# P10_ESP32_1.net
KiCad netlist of a schematic drawn in Altium Designer
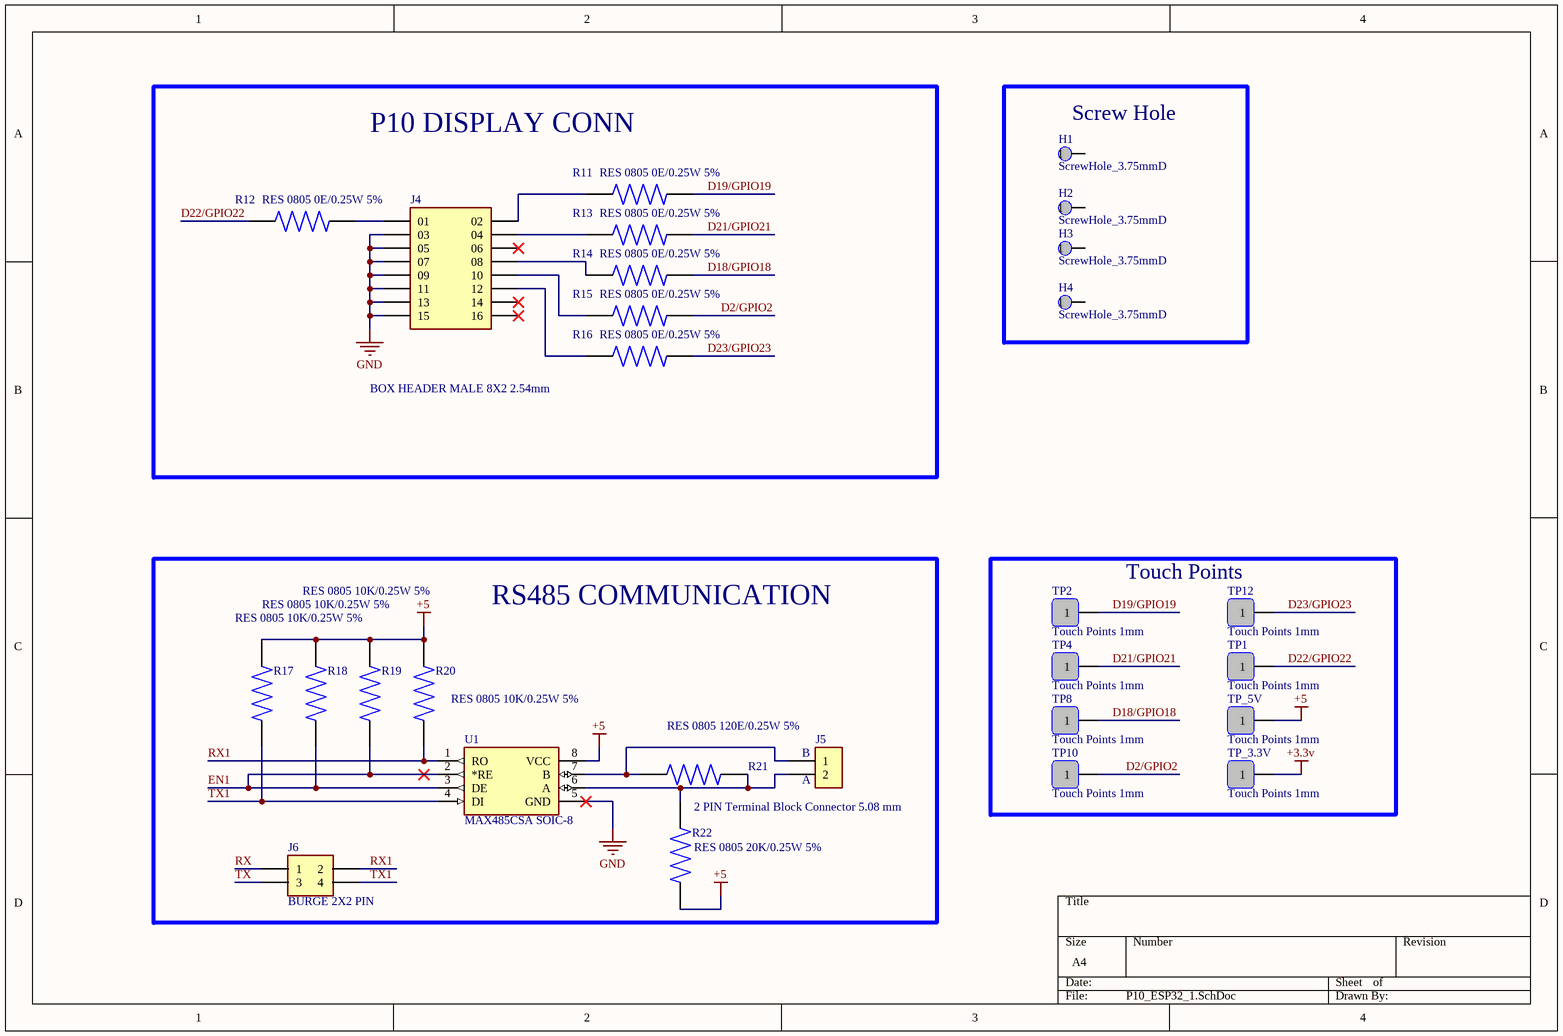
[diagram p0: P10_ESP32_1.SchDoc]

(export (version "E")
  (design (tool "Eeschema 10.0.6"))
  (components
    (comp (ref "H1")
      (value "ScrewHole_3.75mmD")
      (footprint "ScrewHole_3.75mmD")
      (description "SCREW HEAD DIA 4.5MM, SREW LEG DIA 3 MM")
      (libsource (lib "P10_ESP32") (part "ScrewHole_3.75mmD"))
    )
    (comp (ref "H2")
      (value "ScrewHole_3.75mmD")
      (footprint "ScrewHole_3.75mmD")
      (description "SCREW HEAD DIA 4.5MM, SREW LEG DIA 3 MM")
      (libsource (lib "P10_ESP32") (part "ScrewHole_3.75mmD"))
    )
    (comp (ref "H3")
      (value "ScrewHole_3.75mmD")
      (footprint "ScrewHole_3.75mmD")
      (description "SCREW HEAD DIA 4.5MM, SREW LEG DIA 3 MM")
      (libsource (lib "P10_ESP32") (part "ScrewHole_3.75mmD"))
    )
    (comp (ref "H4")
      (value "ScrewHole_3.75mmD")
      (footprint "ScrewHole_3.75mmD")
      (description "SCREW HEAD DIA 4.5MM, SREW LEG DIA 3 MM")
      (libsource (lib "P10_ESP32") (part "ScrewHole_3.75mmD"))
    )
    (comp (ref "J4")
      (value "BOX HEADER MALE 8X2 2.54mm")
      (footprint "BOX HEADER MALE 8X2 2.54mm")
      (description "BOX HEADER MALE 8X2 2.54mm 16 pin")
      (fields (field (name "MP") "TSS-108-01-T-D"))
      (libsource (lib "P10_ATMEGA328P") (part "BOX HEADER MALE 8X2 2.54mm"))
    )
    (comp (ref "J5")
      (value "2 PIN Terminal Block Connector 5.08 mm")
      (footprint "2 PIN Terminal Block Connector 5.08 mm")
      (description "MOLEX,Screw Type, Horizontal, 5.08 Pitch, 24~12 (AWG), Terminal Block Connector, TB007-508-02BE")
      (fields (field (name "MF") "Same Sky") (field (name "MP") "TB007-508-02BE"))
      (libsource (lib "P10_ATMEGA328P") (part "2 PIN Terminal Block Connector 5.08 mm"))
    )
    (comp (ref "J6")
      (value "BURGE 2X2 PIN")
      (footprint "BURGE 2X2 pin")
      (description "Connector Header Through Hole 4 position 0.100 (2.54mm), 2X2 PIN")
      (fields (field (name "MF") "Samtec") (field (name "MP") "MTLW-102-05-G-D-180"))
      (libsource (lib "P10_ATMEGA328P") (part "4PIN BURGE"))
    )
    (comp (ref "R11")
      (value "RES 0805 0E/0.25W 5%")
      (footprint "RES 0805 10K/0.25W 5%")
      (fields (field (name "MP") "ERJ-6GEYJ103V") (field (name "MF") "Panasonic Electronic"))
      (libsource (lib "P10_ATMEGA328P") (part "RES 0805 10K/0.25W 5%"))
    )
    (comp (ref "R12")
      (value "RES 0805 0E/0.25W 5%")
      (footprint "RES 0805 10K/0.25W 5%")
      (fields (field (name "MP") "ERJ-6GEYJ103V") (field (name "MF") "Panasonic Electronic"))
      (libsource (lib "P10_ATMEGA328P") (part "RES 0805 10K/0.25W 5%"))
    )
    (comp (ref "R13")
      (value "RES 0805 0E/0.25W 5%")
      (footprint "RES 0805 10K/0.25W 5%")
      (fields (field (name "MP") "ERJ-6GEYJ103V") (field (name "MF") "Panasonic Electronic"))
      (libsource (lib "P10_ATMEGA328P") (part "RES 0805 10K/0.25W 5%"))
    )
    (comp (ref "R14")
      (value "RES 0805 0E/0.25W 5%")
      (footprint "RES 0805 10K/0.25W 5%")
      (fields (field (name "MP") "ERJ-6GEYJ103V") (field (name "MF") "Panasonic Electronic"))
      (libsource (lib "P10_ATMEGA328P") (part "RES 0805 10K/0.25W 5%"))
    )
    (comp (ref "R15")
      (value "RES 0805 0E/0.25W 5%")
      (footprint "RES 0805 10K/0.25W 5%")
      (fields (field (name "MP") "ERJ-6GEYJ103V") (field (name "MF") "Panasonic Electronic"))
      (libsource (lib "P10_ATMEGA328P") (part "RES 0805 10K/0.25W 5%"))
    )
    (comp (ref "R16")
      (value "RES 0805 0E/0.25W 5%")
      (footprint "RES 0805 10K/0.25W 5%")
      (fields (field (name "MP") "ERJ-6GEYJ103V") (field (name "MF") "Panasonic Electronic"))
      (libsource (lib "P10_ATMEGA328P") (part "RES 0805 10K/0.25W 5%"))
    )
    (comp (ref "R17")
      (value "RES 0805 10K/0.25W 5%")
      (footprint "RES 0805 10K/0.25W 5%")
      (fields (field (name "MP") "ERJ-6GEYJ103V") (field (name "MF") "Panasonic Electronic"))
      (libsource (lib "P10_ATMEGA328P") (part "RES 0805 10K/0.25W 5%"))
    )
    (comp (ref "R18")
      (value "RES 0805 10K/0.25W 5%")
      (footprint "RES 0805 10K/0.25W 5%")
      (fields (field (name "MP") "ERJ-6GEYJ103V") (field (name "MF") "Panasonic Electronic"))
      (libsource (lib "P10_ATMEGA328P") (part "RES 0805 10K/0.25W 5%"))
    )
    (comp (ref "R19")
      (value "RES 0805 10K/0.25W 5%")
      (footprint "RES 0805 10K/0.25W 5%")
      (fields (field (name "MP") "ERJ-6GEYJ103V") (field (name "MF") "Panasonic Electronic"))
      (libsource (lib "P10_ATMEGA328P") (part "RES 0805 10K/0.25W 5%"))
    )
    (comp (ref "R20")
      (value "RES 0805 10K/0.25W 5%")
      (footprint "RES 0805 10K/0.25W 5%")
      (fields (field (name "MP") "ERJ-6GEYJ103V") (field (name "MF") "Panasonic Electronic"))
      (libsource (lib "P10_ATMEGA328P") (part "RES 0805 10K/0.25W 5%"))
    )
    (comp (ref "R21")
      (value "RES 0805 120E/0.25W 5%")
      (footprint "RES 0805 10K/0.25W 5%")
      (fields (field (name "MP") "ERJ-6GEYJ103V") (field (name "MF") "Panasonic Electronic"))
      (libsource (lib "P10_ATMEGA328P") (part "RES 0805 10K/0.25W 5%"))
    )
    (comp (ref "R22")
      (value "RES 0805 20K/0.25W 5%")
      (footprint "RES 0805 10K/0.25W 5%")
      (fields (field (name "MP") "ERJ-6GEYJ103V") (field (name "MF") "Panasonic Electronic"))
      (libsource (lib "P10_ATMEGA328P") (part "RES 0805 10K/0.25W 5%"))
    )
    (comp (ref "TP1")
      (value "Touch Points 1mm")
      (footprint "Touch Points 1mm")
      (description "Touch Points 0.75mm to1mm")
      (libsource (lib "P10_ESP32") (part "Touch Points"))
    )
    (comp (ref "TP2")
      (value "Touch Points 1mm")
      (footprint "Touch Points 1mm")
      (description "Touch Points 0.75mm to1mm")
      (libsource (lib "P10_ESP32") (part "Touch Points"))
    )
    (comp (ref "TP4")
      (value "Touch Points 1mm")
      (footprint "Touch Points 1mm")
      (description "Touch Points 0.75mm to1mm")
      (libsource (lib "P10_ESP32") (part "Touch Points"))
    )
    (comp (ref "TP8")
      (value "Touch Points 1mm")
      (footprint "Touch Points 1mm")
      (description "Touch Points 0.75mm to1mm")
      (libsource (lib "P10_ESP32") (part "Touch Points"))
    )
    (comp (ref "TP10")
      (value "Touch Points 1mm")
      (footprint "Touch Points 1mm")
      (description "Touch Points 0.75mm to1mm")
      (libsource (lib "P10_ESP32") (part "Touch Points"))
    )
    (comp (ref "TP12")
      (value "Touch Points 1mm")
      (footprint "Touch Points 1mm")
      (description "Touch Points 0.75mm to1mm")
      (libsource (lib "P10_ESP32") (part "Touch Points"))
    )
    (comp (ref "TP_3.3V")
      (value "Touch Points 1mm")
      (footprint "Touch Points 1mm")
      (description "Touch Points 0.75mm to1mm")
      (libsource (lib "P10_ESP32") (part "Touch Points"))
    )
    (comp (ref "TP_5V")
      (value "Touch Points 1mm")
      (footprint "Touch Points 1mm")
      (description "Touch Points 0.75mm to1mm")
      (libsource (lib "P10_ESP32") (part "Touch Points"))
    )
    (comp (ref "U1")
      (value "MAX485CSA SOIC-8")
      (footprint "MAX485CSA")
      (description "MAX485CSA-RS-485/RS-422 Transceivers, SOIC-8")
      (fields (field (name "MF") "Analog Devices") (field (name "MP") "MAX485CSA+"))
      (libsource (lib "P10_ATMEGA328P") (part "MAX485CSA"))
    )
  )
  (nets
    (net (code "1") (name "+3.3v") (class "Default")
      (node (ref "TP_3.3V") (pin "1") (pinfunction "1_1") (pintype "passive"))
    )
    (net (code "2") (name "+5") (class "Default")
      (node (ref "R17") (pin "2") (pinfunction "2_2") (pintype "passive"))
      (node (ref "R18") (pin "2") (pinfunction "2_2") (pintype "passive"))
      (node (ref "R19") (pin "2") (pinfunction "2_2") (pintype "passive"))
      (node (ref "R20") (pin "2") (pinfunction "2_2") (pintype "passive"))
      (node (ref "R22") (pin "1") (pinfunction "1_1") (pintype "passive"))
      (node (ref "TP_5V") (pin "1") (pinfunction "1_1") (pintype "passive"))
      (node (ref "U1") (pin "8") (pinfunction "VCC_8") (pintype "power_in"))
    )
    (net (code "3") (name "/D2{slash}GPIO2") (class "Default")
      (node (ref "R15") (pin "2") (pinfunction "2_2") (pintype "passive"))
      (node (ref "TP10") (pin "1") (pinfunction "1_1") (pintype "passive"))
    )
    (net (code "4") (name "/D18{slash}GPIO18") (class "Default")
      (node (ref "R14") (pin "2") (pinfunction "2_2") (pintype "passive"))
      (node (ref "TP8") (pin "1") (pinfunction "1_1") (pintype "passive"))
    )
    (net (code "5") (name "/D19{slash}GPIO19") (class "Default")
      (node (ref "R11") (pin "2") (pinfunction "2_2") (pintype "passive"))
      (node (ref "TP2") (pin "1") (pinfunction "1_1") (pintype "passive"))
    )
    (net (code "6") (name "/D21{slash}GPIO21") (class "Default")
      (node (ref "R13") (pin "2") (pinfunction "2_2") (pintype "passive"))
      (node (ref "TP4") (pin "1") (pinfunction "1_1") (pintype "passive"))
    )
    (net (code "7") (name "/D22{slash}GPIO22") (class "Default")
      (node (ref "R12") (pin "1") (pinfunction "1_1") (pintype "passive"))
      (node (ref "TP1") (pin "1") (pinfunction "1_1") (pintype "passive"))
    )
    (net (code "8") (name "/D23{slash}GPIO23") (class "Default")
      (node (ref "R16") (pin "2") (pinfunction "2_2") (pintype "passive"))
      (node (ref "TP12") (pin "1") (pinfunction "1_1") (pintype "passive"))
    )
    (net (code "9") (name "/EN1") (class "Default")
      (node (ref "R18") (pin "1") (pinfunction "1_1") (pintype "passive"))
      (node (ref "R19") (pin "1") (pinfunction "1_1") (pintype "passive"))
      (node (ref "U1") (pin "2") (pinfunction "*RE_2") (pintype "output"))
      (node (ref "U1") (pin "3") (pinfunction "DE_3") (pintype "output"))
    )
    (net (code "10") (name "/RX") (class "Default")
      (node (ref "J6") (pin "01") (pinfunction "1_01") (pintype "passive"))
    )
    (net (code "11") (name "/RX1") (class "Default")
      (node (ref "J6") (pin "02") (pinfunction "2_02") (pintype "passive"))
      (node (ref "R20") (pin "1") (pinfunction "1_1") (pintype "passive"))
      (node (ref "U1") (pin "1") (pinfunction "RO_1") (pintype "output"))
    )
    (net (code "12") (name "/TX") (class "Default")
      (node (ref "J6") (pin "03") (pinfunction "3_03") (pintype "passive"))
    )
    (net (code "13") (name "/TX1") (class "Default")
      (node (ref "J6") (pin "04") (pinfunction "4_04") (pintype "passive"))
      (node (ref "R17") (pin "1") (pinfunction "1_1") (pintype "passive"))
      (node (ref "U1") (pin "4") (pinfunction "DI_4") (pintype "input"))
    )
    (net (code "14") (name "GND") (class "Default")
      (node (ref "J4") (pin "03") (pinfunction "03_03") (pintype "passive"))
      (node (ref "J4") (pin "05") (pinfunction "05_05") (pintype "passive"))
      (node (ref "J4") (pin "07") (pinfunction "07_07") (pintype "passive"))
      (node (ref "J4") (pin "09") (pinfunction "09_09") (pintype "passive"))
      (node (ref "J4") (pin "11") (pinfunction "11_11") (pintype "passive"))
      (node (ref "J4") (pin "13") (pinfunction "13_13") (pintype "passive"))
      (node (ref "J4") (pin "15") (pinfunction "15_15") (pintype "passive"))
      (node (ref "U1") (pin "5") (pinfunction "GND_5") (pintype "power_in"))
    )
    (net (code "15") (name "Net-(J4-Pad01)") (class "Default")
      (node (ref "J4") (pin "01") (pinfunction "01_01") (pintype "passive"))
      (node (ref "R12") (pin "2") (pinfunction "2_2") (pintype "passive"))
    )
    (net (code "16") (name "Net-(J4-Pad02)") (class "Default")
      (node (ref "J4") (pin "02") (pinfunction "02_02") (pintype "passive"))
      (node (ref "R11") (pin "1") (pinfunction "1_1") (pintype "passive"))
    )
    (net (code "17") (name "Net-(J4-Pad04)") (class "Default")
      (node (ref "J4") (pin "04") (pinfunction "04_04") (pintype "passive"))
      (node (ref "R13") (pin "1") (pinfunction "1_1") (pintype "passive"))
    )
    (net (code "18") (name "Net-(J4-Pad08)") (class "Default")
      (node (ref "J4") (pin "08") (pinfunction "08_08") (pintype "passive"))
      (node (ref "R14") (pin "1") (pinfunction "1_1") (pintype "passive"))
    )
    (net (code "19") (name "Net-(J4-Pad10)") (class "Default")
      (node (ref "J4") (pin "10") (pinfunction "10_10") (pintype "passive"))
      (node (ref "R15") (pin "1") (pinfunction "1_1") (pintype "passive"))
    )
    (net (code "20") (name "Net-(J4-Pad12)") (class "Default")
      (node (ref "J4") (pin "12") (pinfunction "12_12") (pintype "passive"))
      (node (ref "R16") (pin "1") (pinfunction "1_1") (pintype "passive"))
    )
    (net (code "21") (name "Net-(U1-A)") (class "Default")
      (node (ref "J5") (pin "2") (pinfunction "2_2") (pintype "passive"))
      (node (ref "R21") (pin "2") (pinfunction "2_2") (pintype "passive"))
      (node (ref "R22") (pin "2") (pinfunction "2_2") (pintype "passive"))
      (node (ref "U1") (pin "6") (pinfunction "A_6") (pintype "bidirectional"))
    )
    (net (code "22") (name "Net-(U1-B)") (class "Default")
      (node (ref "J5") (pin "1") (pinfunction "1_1") (pintype "passive"))
      (node (ref "R21") (pin "1") (pinfunction "1_1") (pintype "passive"))
      (node (ref "U1") (pin "7") (pinfunction "B_7") (pintype "bidirectional"))
    )
    (net (code "23") (name "unconnected-(H1-Pad1)") (class "Default")
      (node (ref "H1") (pin "1") (pinfunction "1_1") (pintype "passive"))
    )
    (net (code "24") (name "unconnected-(H2-Pad1)") (class "Default")
      (node (ref "H2") (pin "1") (pinfunction "1_1") (pintype "passive"))
    )
    (net (code "25") (name "unconnected-(H3-Pad1)") (class "Default")
      (node (ref "H3") (pin "1") (pinfunction "1_1") (pintype "passive"))
    )
    (net (code "26") (name "unconnected-(H4-Pad1)") (class "Default")
      (node (ref "H4") (pin "1") (pinfunction "1_1") (pintype "passive"))
    )
    (net (code "27") (name "unconnected-(J4-Pad06)") (class "Default")
      (node (ref "J4") (pin "06") (pinfunction "06_06") (pintype "passive+no_connect"))
    )
    (net (code "28") (name "unconnected-(J4-Pad14)") (class "Default")
      (node (ref "J4") (pin "14") (pinfunction "14_14") (pintype "passive+no_connect"))
    )
    (net (code "29") (name "unconnected-(J4-Pad16)") (class "Default")
      (node (ref "J4") (pin "16") (pinfunction "16_16") (pintype "passive+no_connect"))
    )
  )
)
